# 10_isolator.net
KiCad netlist of a schematic drawn in Altium Designer
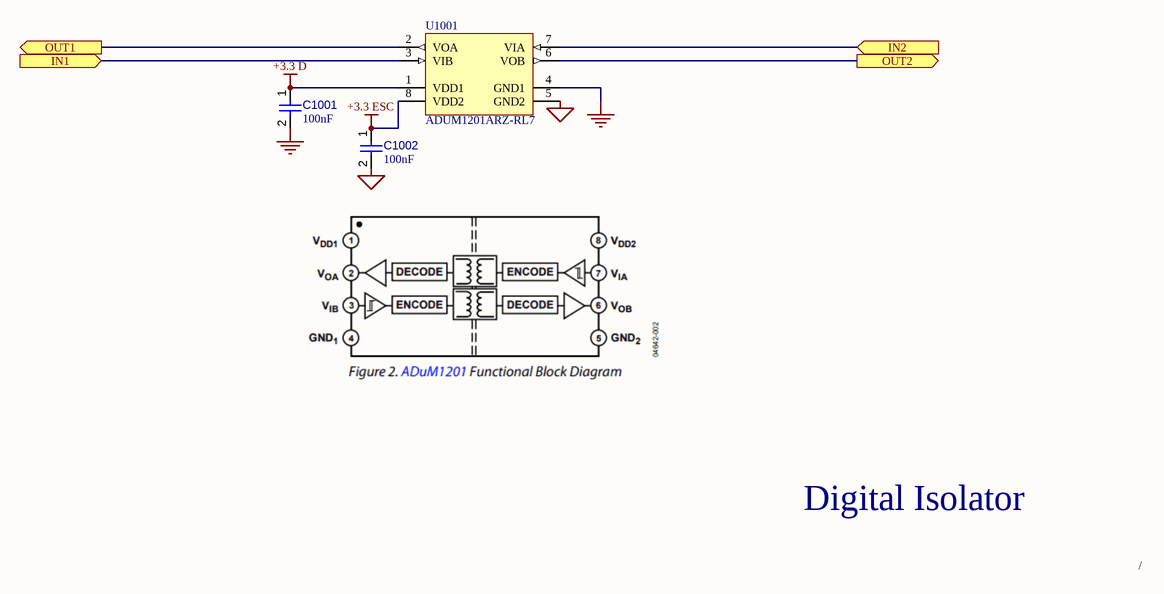
[diagram p0: 10 isolator.SchDoc]

(export (version "E")
  (design (tool "Eeschema 10.0.6"))
  (components
    (comp (ref "C1001")
      (value "100nF")
      (footprint "CAPC0402(1005)60_L")
      (description "Chip Capacitor, 100nF +/-20%, 25V, 0402, Thickness 0.6 mm")
      (fields (field (name "TOLERANCE") "10%") (field (name "Comment") "Capacitor 100nF +/-20% 25V 0402"))
      (libsource (lib "UBC Uncrewed Aircraft Systems") (part "CAP-NP-2"))
    )
    (comp (ref "C1002")
      (value "100nF")
      (footprint "CAPC0402(1005)60_L")
      (description "Chip Capacitor, 100nF +/-20%, 25V, 0402, Thickness 0.6 mm")
      (fields (field (name "TOLERANCE") "10%") (field (name "Comment") "Capacitor 100nF +/-20% 25V 0402"))
      (libsource (lib "UBC Uncrewed Aircraft Systems") (part "CAP-NP-2"))
    )
    (comp (ref "U1001")
      (value "ADUM1201ARZ-RL7")
      (footprint "ADI-R-8_L")
      (fields (field (name "MANUFACTURER") "Analog Devices"))
      (libsource (lib "Altium Content Vault") (part "ADI-ADUM1201-R-8"))
    )
  )
  (nets
    (net (code "1") (name "+3.3 D") (class "Default")
      (node (ref "C1001") (pin "1") (pinfunction "1_1") (pintype "passive"))
      (node (ref "U1001") (pin "1") (pinfunction "VDD1_1") (pintype "power_in"))
    )
    (net (code "2") (name "+3.3 ESC") (class "Default")
      (node (ref "C1002") (pin "1") (pinfunction "1_1") (pintype "passive"))
      (node (ref "U1001") (pin "8") (pinfunction "VDD2_8") (pintype "power_in"))
    )
    (net (code "3") (name "/IN1") (class "Default")
      (node (ref "U1001") (pin "3") (pinfunction "VIB_3") (pintype "input"))
    )
    (net (code "4") (name "/IN2") (class "Default")
      (node (ref "U1001") (pin "7") (pinfunction "VIA_7") (pintype "input"))
    )
    (net (code "5") (name "/OUT1") (class "Default")
      (node (ref "U1001") (pin "2") (pinfunction "VOA_2") (pintype "output"))
    )
    (net (code "6") (name "/OUT2") (class "Default")
      (node (ref "U1001") (pin "6") (pinfunction "VOB_6") (pintype "output"))
    )
    (net (code "7") (name "GND") (class "Default")
      (node (ref "C1001") (pin "2") (pinfunction "2_2") (pintype "passive"))
      (node (ref "U1001") (pin "4") (pinfunction "GND1_4") (pintype "power_in"))
    )
    (net (code "8") (name "PGND") (class "Default")
      (node (ref "C1002") (pin "2") (pinfunction "2_2") (pintype "passive"))
      (node (ref "U1001") (pin "5") (pinfunction "GND2_5") (pintype "power_in"))
    )
  )
)
